# ab73287.net
KiCad netlist of a schematic drawn in EAGLE
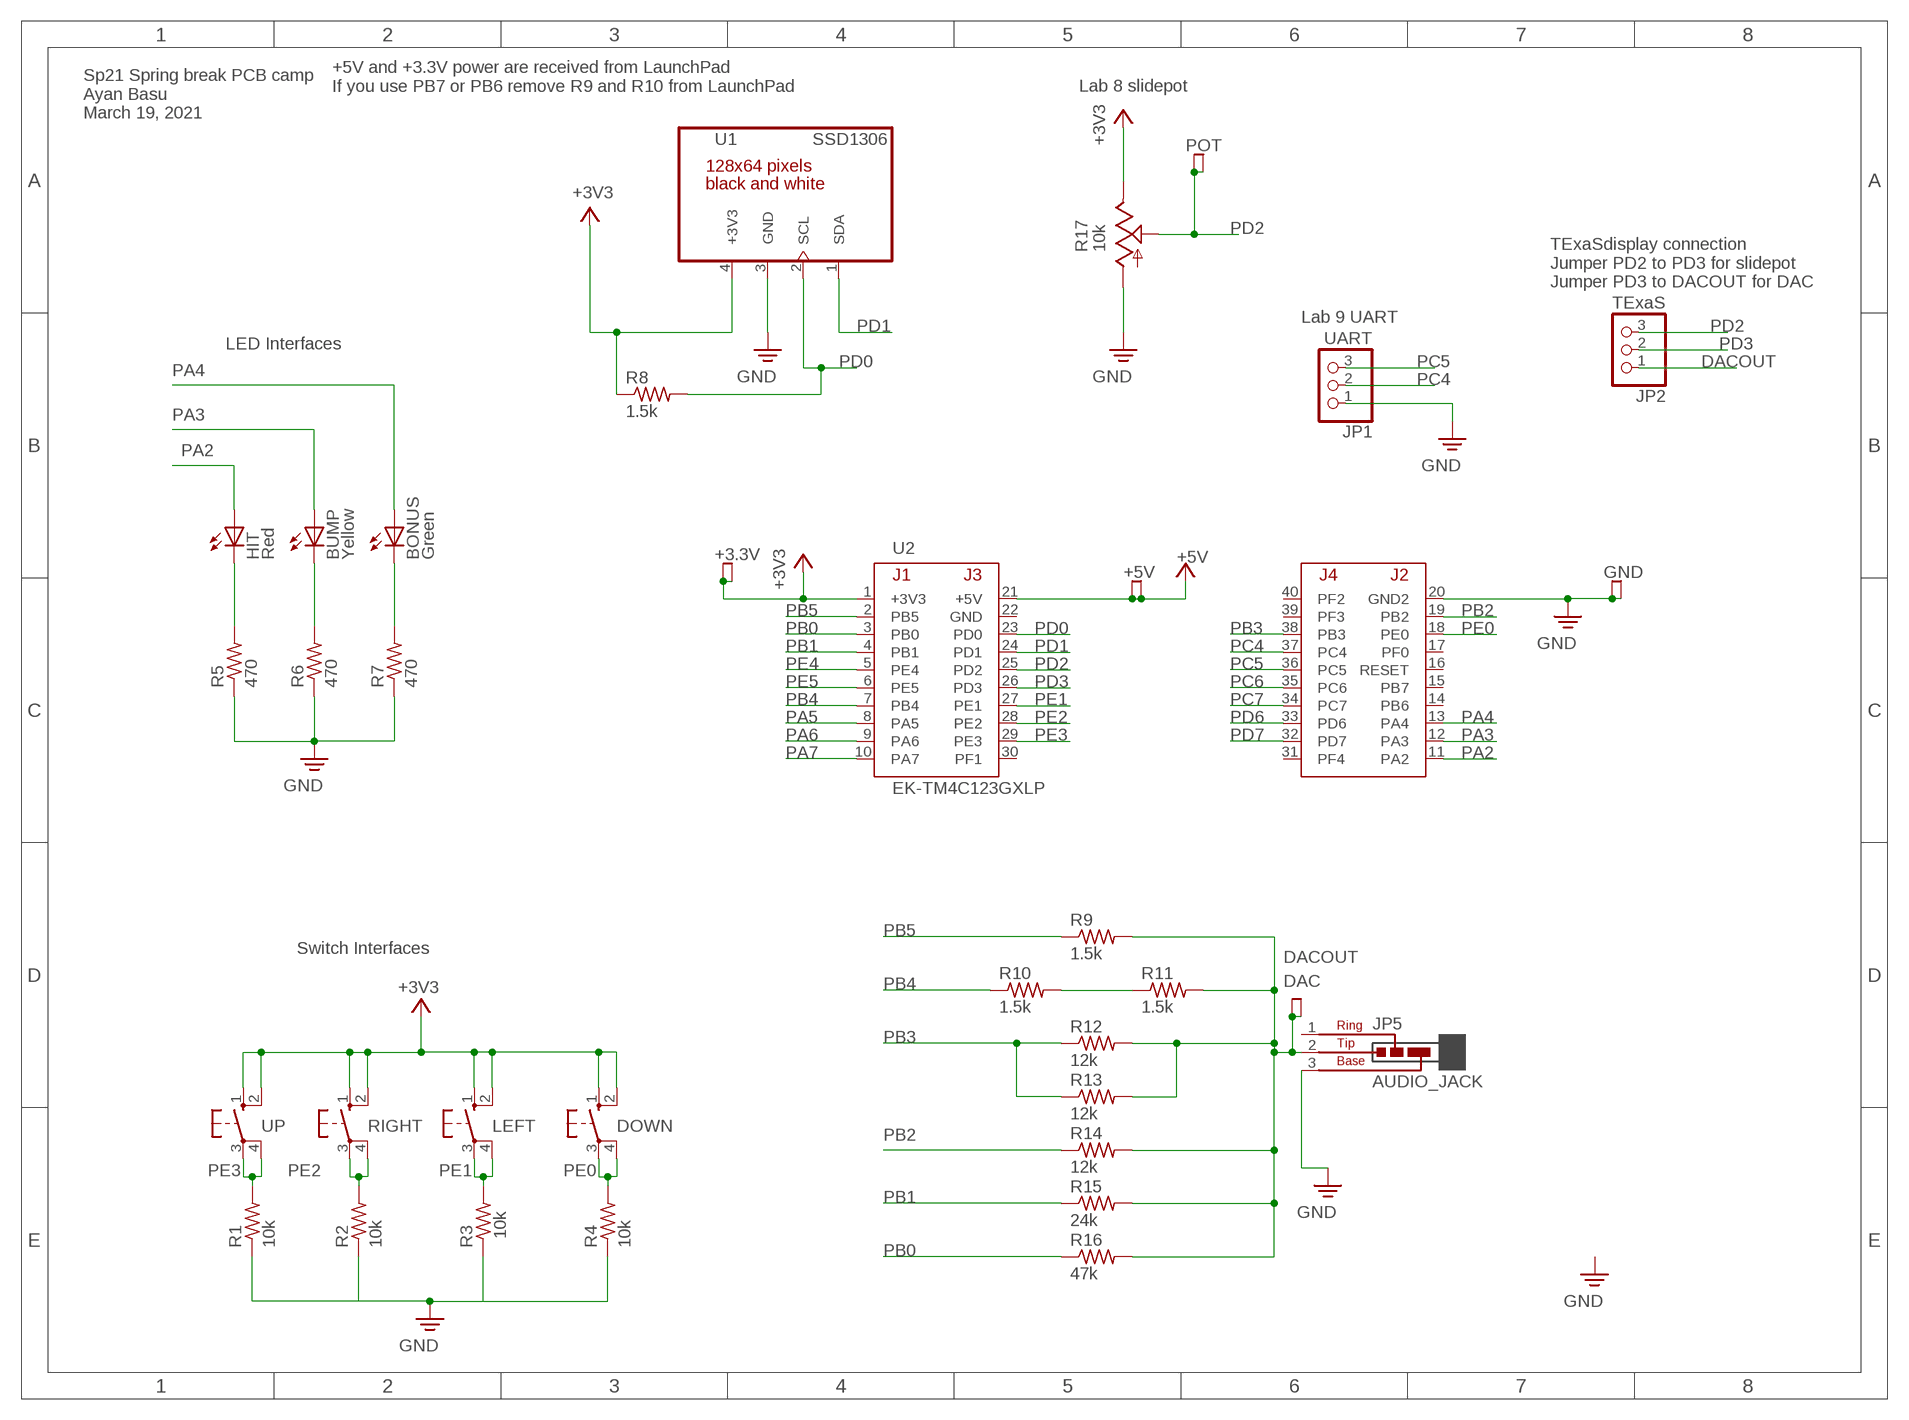
[diagram p0: schematic, sheet 1]

(export (version "E")
  (design (tool "Eeschema 10.0.6"))
  (components
    (comp (ref "+3.3V")
      (value "TP2")
      (footprint "eagle-import:TP2")
      (libsource (lib "eagle-import") (part "TP2"))
    )
    (comp (ref "+5V")
      (value "TP2")
      (footprint "eagle-import:TP2")
      (libsource (lib "eagle-import") (part "TP2"))
    )
    (comp (ref "BONUS")
      (value "Green")
      (footprint "eagle-import:LED5MM")
      (libsource (lib "eagle-import") (part "LED5MM"))
    )
    (comp (ref "BUMP")
      (value "Yellow")
      (footprint "eagle-import:LED5MM")
      (libsource (lib "eagle-import") (part "LED5MM"))
    )
    (comp (ref "DAC")
      (value "TP2")
      (footprint "eagle-import:TP2")
      (libsource (lib "eagle-import") (part "TP2"))
    )
    (comp (ref "DOWN")
      (value "B3F-1052")
      (footprint "eagle-import:B3F-10XX")
      (fields (field (name "MPN") "B3F-1000"))
      (libsource (lib "eagle-import") (part "B3F-1052"))
    )
    (comp (ref "GND")
      (value "TP2")
      (footprint "eagle-import:TP2")
      (libsource (lib "eagle-import") (part "TP2"))
    )
    (comp (ref "HIT")
      (value "Red")
      (footprint "eagle-import:LED5MM")
      (libsource (lib "eagle-import") (part "LED5MM"))
    )
    (comp (ref "JP1")
      (value "UART")
      (footprint "eagle-import:1X03")
      (libsource (lib "eagle-import") (part "PINHD-1X3"))
    )
    (comp (ref "JP2")
      (value "TExaS")
      (footprint "eagle-import:1X03")
      (libsource (lib "eagle-import") (part "PINHD-1X3"))
    )
    (comp (ref "JP5")
      (value "AUDIO_JACK")
      (footprint "eagle-import:JACK")
      (libsource (lib "eagle-import") (part "AUDIO_JACK"))
    )
    (comp (ref "LEFT")
      (value "B3F-1052")
      (footprint "eagle-import:B3F-10XX")
      (fields (field (name "MPN") "B3F-1000"))
      (libsource (lib "eagle-import") (part "B3F-1052"))
    )
    (comp (ref "POT")
      (value "TP2")
      (footprint "eagle-import:TP2")
      (libsource (lib "eagle-import") (part "TP2"))
    )
    (comp (ref "R1")
      (value "10k")
      (footprint "eagle-import:RES300MIL")
      (libsource (lib "eagle-import") (part "RESISTOR0204/7"))
    )
    (comp (ref "R2")
      (value "10k")
      (footprint "eagle-import:RES300MIL")
      (libsource (lib "eagle-import") (part "RESISTOR0204/7"))
    )
    (comp (ref "R3")
      (value "10k")
      (footprint "eagle-import:RES300MIL")
      (libsource (lib "eagle-import") (part "RESISTOR0204/7"))
    )
    (comp (ref "R4")
      (value "10k")
      (footprint "eagle-import:RES300MIL")
      (libsource (lib "eagle-import") (part "RESISTOR0204/7"))
    )
    (comp (ref "R5")
      (value "470")
      (footprint "eagle-import:RES300MIL")
      (libsource (lib "eagle-import") (part "RESISTOR0204/7"))
    )
    (comp (ref "R6")
      (value "470")
      (footprint "eagle-import:RES300MIL")
      (libsource (lib "eagle-import") (part "RESISTOR0204/7"))
    )
    (comp (ref "R7")
      (value "470")
      (footprint "eagle-import:RES300MIL")
      (libsource (lib "eagle-import") (part "RESISTOR0204/7"))
    )
    (comp (ref "R8")
      (value "1.5k")
      (footprint "eagle-import:RES300MIL")
      (libsource (lib "eagle-import") (part "RESISTOR0204/7"))
    )
    (comp (ref "R9")
      (value "1.5k")
      (footprint "eagle-import:RES300MIL")
      (libsource (lib "eagle-import") (part "RESISTOR0204/7"))
    )
    (comp (ref "R10")
      (value "1.5k")
      (footprint "eagle-import:RES300MIL")
      (libsource (lib "eagle-import") (part "RESISTOR0204/7"))
    )
    (comp (ref "R11")
      (value "1.5k")
      (footprint "eagle-import:RES300MIL")
      (libsource (lib "eagle-import") (part "RESISTOR0204/7"))
    )
    (comp (ref "R12")
      (value "12k")
      (footprint "eagle-import:RES300MIL")
      (libsource (lib "eagle-import") (part "RESISTOR0204/7"))
    )
    (comp (ref "R13")
      (value "12k")
      (footprint "eagle-import:RES300MIL")
      (libsource (lib "eagle-import") (part "RESISTOR0204/7"))
    )
    (comp (ref "R14")
      (value "12k")
      (footprint "eagle-import:RES300MIL")
      (libsource (lib "eagle-import") (part "RESISTOR0204/7"))
    )
    (comp (ref "R15")
      (value "24k")
      (footprint "eagle-import:RES300MIL")
      (libsource (lib "eagle-import") (part "RESISTOR0204/7"))
    )
    (comp (ref "R16")
      (value "47k")
      (footprint "eagle-import:RES300MIL")
      (libsource (lib "eagle-import") (part "RESISTOR0204/7"))
    )
    (comp (ref "R17")
      (value "10k")
      (footprint "eagle-import:B25U")
      (libsource (lib "eagle-import") (part "POTENTIOMETERB25U"))
    )
    (comp (ref "RIGHT")
      (value "B3F-1052")
      (footprint "eagle-import:B3F-10XX")
      (fields (field (name "MPN") "B3F-1000"))
      (libsource (lib "eagle-import") (part "B3F-1052"))
    )
    (comp (ref "U1")
      (value "SSD1306")
      (footprint "eagle-import:SSD1306")
      (libsource (lib "eagle-import") (part "SSD1306"))
    )
    (comp (ref "U2")
      (value "EK-TM4C123GXLP")
      (footprint "eagle-import:TM4C123LAUNCHPAD")
      (libsource (lib "eagle-import") (part "EK-TM4C123GXLP"))
    )
    (comp (ref "UP")
      (value "B3F-1052")
      (footprint "eagle-import:B3F-10XX")
      (fields (field (name "MPN") "B3F-1000"))
      (libsource (lib "eagle-import") (part "B3F-1052"))
    )
  )
  (nets
    (net (code "1") (name "+3V3") (class "Default")
      (node (ref "+3.3V") (pin "MP") (pinfunction "TPA_MP") (pintype "passive"))
      (node (ref "+3.3V") (pin "MP1") (pinfunction "TPB_MP1") (pintype "passive"))
      (node (ref "DOWN") (pin "1") (pinfunction "S_1") (pintype "passive"))
      (node (ref "DOWN") (pin "2") (pinfunction "S1_2") (pintype "passive"))
      (node (ref "LEFT") (pin "1") (pinfunction "S_1") (pintype "passive"))
      (node (ref "LEFT") (pin "2") (pinfunction "S1_2") (pintype "passive"))
      (node (ref "R17") (pin "1") (pinfunction "E_1") (pintype "passive"))
      (node (ref "R8") (pin "1") (pinfunction "1_1") (pintype "passive"))
      (node (ref "RIGHT") (pin "1") (pinfunction "S_1") (pintype "passive"))
      (node (ref "RIGHT") (pin "2") (pinfunction "S1_2") (pintype "passive"))
      (node (ref "U1") (pin "4") (pinfunction "+3V3_4") (pintype "power_in"))
      (node (ref "U2") (pin "1") (pinfunction "+3V3_1") (pintype "bidirectional"))
      (node (ref "UP") (pin "1") (pinfunction "S_1") (pintype "passive"))
      (node (ref "UP") (pin "2") (pinfunction "S1_2") (pintype "passive"))
    )
    (net (code "2") (name "+5V") (class "Default")
      (node (ref "+5V") (pin "MP") (pinfunction "TPA_MP") (pintype "passive"))
      (node (ref "+5V") (pin "MP1") (pinfunction "TPB_MP1") (pintype "passive"))
      (node (ref "U2") (pin "21") (pinfunction "+5V_21") (pintype "bidirectional"))
    )
    (net (code "3") (name "/DACOUT") (class "Default")
      (node (ref "DAC") (pin "MP") (pinfunction "TPA_MP") (pintype "passive"))
      (node (ref "DAC") (pin "MP1") (pinfunction "TPB_MP1") (pintype "passive"))
      (node (ref "JP2") (pin "1") (pinfunction "1_1") (pintype "passive"))
      (node (ref "JP5") (pin "2") (pinfunction "TIP_2") (pintype "passive"))
      (node (ref "R11") (pin "2") (pinfunction "2_2") (pintype "passive"))
      (node (ref "R12") (pin "2") (pinfunction "2_2") (pintype "passive"))
      (node (ref "R13") (pin "2") (pinfunction "2_2") (pintype "passive"))
      (node (ref "R14") (pin "2") (pinfunction "2_2") (pintype "passive"))
      (node (ref "R15") (pin "2") (pinfunction "2_2") (pintype "passive"))
      (node (ref "R16") (pin "2") (pinfunction "2_2") (pintype "passive"))
      (node (ref "R9") (pin "2") (pinfunction "2_2") (pintype "passive"))
    )
    (net (code "4") (name "/PA2") (class "Default")
      (node (ref "HIT") (pin "A") (pinfunction "A_A") (pintype "passive"))
      (node (ref "U2") (pin "11") (pinfunction "PA2_11") (pintype "bidirectional"))
    )
    (net (code "5") (name "/PA3") (class "Default")
      (node (ref "BUMP") (pin "A") (pinfunction "A_A") (pintype "passive"))
      (node (ref "U2") (pin "12") (pinfunction "PA3_12") (pintype "bidirectional"))
    )
    (net (code "6") (name "/PA4") (class "Default")
      (node (ref "BONUS") (pin "A") (pinfunction "A_A") (pintype "passive"))
      (node (ref "U2") (pin "13") (pinfunction "PA4_13") (pintype "bidirectional"))
    )
    (net (code "7") (name "/PA5") (class "Default")
      (node (ref "U2") (pin "8") (pinfunction "PA5_8") (pintype "bidirectional"))
    )
    (net (code "8") (name "/PA6") (class "Default")
      (node (ref "U2") (pin "9") (pinfunction "PA6_9") (pintype "bidirectional"))
    )
    (net (code "9") (name "/PA7") (class "Default")
      (node (ref "U2") (pin "10") (pinfunction "PA7_10") (pintype "bidirectional"))
    )
    (net (code "10") (name "/PB0") (class "Default")
      (node (ref "R16") (pin "1") (pinfunction "1_1") (pintype "passive"))
      (node (ref "U2") (pin "3") (pinfunction "PB0_3") (pintype "bidirectional"))
    )
    (net (code "11") (name "/PB1") (class "Default")
      (node (ref "R15") (pin "1") (pinfunction "1_1") (pintype "passive"))
      (node (ref "U2") (pin "4") (pinfunction "PB1_4") (pintype "bidirectional"))
    )
    (net (code "12") (name "/PB2") (class "Default")
      (node (ref "R14") (pin "1") (pinfunction "1_1") (pintype "passive"))
      (node (ref "U2") (pin "19") (pinfunction "PB2_19") (pintype "bidirectional"))
    )
    (net (code "13") (name "/PB3") (class "Default")
      (node (ref "R12") (pin "1") (pinfunction "1_1") (pintype "passive"))
      (node (ref "R13") (pin "1") (pinfunction "1_1") (pintype "passive"))
      (node (ref "U2") (pin "38") (pinfunction "PB3_38") (pintype "bidirectional"))
    )
    (net (code "14") (name "/PB4") (class "Default")
      (node (ref "R10") (pin "1") (pinfunction "1_1") (pintype "passive"))
      (node (ref "U2") (pin "7") (pinfunction "PB4_7") (pintype "bidirectional"))
    )
    (net (code "15") (name "/PB5") (class "Default")
      (node (ref "R9") (pin "1") (pinfunction "1_1") (pintype "passive"))
      (node (ref "U2") (pin "2") (pinfunction "PB5_2") (pintype "bidirectional"))
    )
    (net (code "16") (name "/PC4") (class "Default")
      (node (ref "JP1") (pin "2") (pinfunction "2_2") (pintype "passive"))
      (node (ref "U2") (pin "37") (pinfunction "PC4_37") (pintype "bidirectional"))
    )
    (net (code "17") (name "/PC5") (class "Default")
      (node (ref "JP1") (pin "3") (pinfunction "3_3") (pintype "passive"))
      (node (ref "U2") (pin "36") (pinfunction "PC5_36") (pintype "bidirectional"))
    )
    (net (code "18") (name "/PC6") (class "Default")
      (node (ref "U2") (pin "35") (pinfunction "PC6_35") (pintype "bidirectional"))
    )
    (net (code "19") (name "/PC7") (class "Default")
      (node (ref "U2") (pin "34") (pinfunction "PC7_34") (pintype "bidirectional"))
    )
    (net (code "20") (name "/PD0") (class "Default")
      (node (ref "R8") (pin "2") (pinfunction "2_2") (pintype "passive"))
      (node (ref "U1") (pin "2") (pinfunction "SCL_2") (pintype "input"))
      (node (ref "U2") (pin "23") (pinfunction "PD0_23") (pintype "bidirectional"))
    )
    (net (code "21") (name "/PD1") (class "Default")
      (node (ref "U1") (pin "1") (pinfunction "SDA_1") (pintype "input"))
      (node (ref "U2") (pin "24") (pinfunction "PD1_24") (pintype "bidirectional"))
    )
    (net (code "22") (name "/PD2") (class "Default")
      (node (ref "JP2") (pin "3") (pinfunction "3_3") (pintype "passive"))
      (node (ref "POT") (pin "MP") (pinfunction "TPA_MP") (pintype "passive"))
      (node (ref "POT") (pin "MP1") (pinfunction "TPB_MP1") (pintype "passive"))
      (node (ref "R17") (pin "2") (pinfunction "S_2") (pintype "passive"))
      (node (ref "U2") (pin "25") (pinfunction "PD2_25") (pintype "bidirectional"))
    )
    (net (code "23") (name "/PD3") (class "Default")
      (node (ref "JP2") (pin "2") (pinfunction "2_2") (pintype "passive"))
      (node (ref "U2") (pin "26") (pinfunction "PD3_26") (pintype "bidirectional"))
    )
    (net (code "24") (name "/PD6") (class "Default")
      (node (ref "U2") (pin "33") (pinfunction "PD6_33") (pintype "bidirectional"))
    )
    (net (code "25") (name "/PD7") (class "Default")
      (node (ref "U2") (pin "32") (pinfunction "PD7_32") (pintype "bidirectional"))
    )
    (net (code "26") (name "/PE0") (class "Default")
      (node (ref "DOWN") (pin "3") (pinfunction "P_3") (pintype "passive"))
      (node (ref "DOWN") (pin "4") (pinfunction "P1_4") (pintype "passive"))
      (node (ref "R4") (pin "2") (pinfunction "2_2") (pintype "passive"))
      (node (ref "U2") (pin "18") (pinfunction "PE0_18") (pintype "bidirectional"))
    )
    (net (code "27") (name "/PE1") (class "Default")
      (node (ref "LEFT") (pin "3") (pinfunction "P_3") (pintype "passive"))
      (node (ref "LEFT") (pin "4") (pinfunction "P1_4") (pintype "passive"))
      (node (ref "R3") (pin "2") (pinfunction "2_2") (pintype "passive"))
      (node (ref "U2") (pin "27") (pinfunction "PE1_27") (pintype "bidirectional"))
    )
    (net (code "28") (name "/PE2") (class "Default")
      (node (ref "R2") (pin "2") (pinfunction "2_2") (pintype "passive"))
      (node (ref "RIGHT") (pin "3") (pinfunction "P_3") (pintype "passive"))
      (node (ref "RIGHT") (pin "4") (pinfunction "P1_4") (pintype "passive"))
      (node (ref "U2") (pin "28") (pinfunction "PE2_28") (pintype "bidirectional"))
    )
    (net (code "29") (name "/PE3") (class "Default")
      (node (ref "R1") (pin "2") (pinfunction "2_2") (pintype "passive"))
      (node (ref "U2") (pin "29") (pinfunction "PE3_29") (pintype "bidirectional"))
      (node (ref "UP") (pin "3") (pinfunction "P_3") (pintype "passive"))
      (node (ref "UP") (pin "4") (pinfunction "P1_4") (pintype "passive"))
    )
    (net (code "30") (name "/PE4") (class "Default")
      (node (ref "U2") (pin "5") (pinfunction "PE4_5") (pintype "bidirectional"))
    )
    (net (code "31") (name "/PE5") (class "Default")
      (node (ref "U2") (pin "6") (pinfunction "PE5_6") (pintype "bidirectional"))
    )
    (net (code "32") (name "GND") (class "Default")
      (node (ref "GND") (pin "MP") (pinfunction "TPA_MP") (pintype "passive"))
      (node (ref "GND") (pin "MP1") (pinfunction "TPB_MP1") (pintype "passive"))
      (node (ref "JP1") (pin "1") (pinfunction "1_1") (pintype "passive"))
      (node (ref "JP5") (pin "3") (pinfunction "BASE_3") (pintype "passive"))
      (node (ref "R1") (pin "1") (pinfunction "1_1") (pintype "passive"))
      (node (ref "R17") (pin "3") (pinfunction "A_3") (pintype "passive"))
      (node (ref "R2") (pin "1") (pinfunction "1_1") (pintype "passive"))
      (node (ref "R3") (pin "1") (pinfunction "1_1") (pintype "passive"))
      (node (ref "R4") (pin "1") (pinfunction "1_1") (pintype "passive"))
      (node (ref "R5") (pin "1") (pinfunction "1_1") (pintype "passive"))
      (node (ref "R6") (pin "1") (pinfunction "1_1") (pintype "passive"))
      (node (ref "R7") (pin "1") (pinfunction "1_1") (pintype "passive"))
      (node (ref "U1") (pin "3") (pinfunction "GND_3") (pintype "power_in"))
      (node (ref "U2") (pin "20") (pinfunction "GND2_20") (pintype "bidirectional"))
    )
    (net (code "33") (name "Net-(BONUS-C)") (class "Default")
      (node (ref "BONUS") (pin "K") (pinfunction "C_K") (pintype "passive"))
      (node (ref "R7") (pin "2") (pinfunction "2_2") (pintype "passive"))
    )
    (net (code "34") (name "Net-(BUMP-C)") (class "Default")
      (node (ref "BUMP") (pin "K") (pinfunction "C_K") (pintype "passive"))
      (node (ref "R6") (pin "2") (pinfunction "2_2") (pintype "passive"))
    )
    (net (code "35") (name "Net-(HIT-C)") (class "Default")
      (node (ref "HIT") (pin "K") (pinfunction "C_K") (pintype "passive"))
      (node (ref "R5") (pin "2") (pinfunction "2_2") (pintype "passive"))
    )
    (net (code "36") (name "Net-(R10-Pad2)") (class "Default")
      (node (ref "R10") (pin "2") (pinfunction "2_2") (pintype "passive"))
      (node (ref "R11") (pin "1") (pinfunction "1_1") (pintype "passive"))
    )
    (net (code "37") (name "unconnected-(JP5-RING-Pad1)") (class "Default")
      (node (ref "JP5") (pin "1") (pinfunction "RING_1") (pintype "passive"))
    )
    (net (code "38") (name "unconnected-(U2-GND-Pad22)") (class "Default")
      (node (ref "U2") (pin "22") (pinfunction "GND_22") (pintype "bidirectional"))
    )
    (net (code "39") (name "unconnected-(U2-PB6-Pad14)") (class "Default")
      (node (ref "U2") (pin "14") (pinfunction "PB6_14") (pintype "bidirectional"))
    )
    (net (code "40") (name "unconnected-(U2-PB7-Pad15)") (class "Default")
      (node (ref "U2") (pin "15") (pinfunction "PB7_15") (pintype "bidirectional"))
    )
    (net (code "41") (name "unconnected-(U2-PF0-Pad17)") (class "Default")
      (node (ref "U2") (pin "17") (pinfunction "PF0_17") (pintype "bidirectional"))
    )
    (net (code "42") (name "unconnected-(U2-PF1-Pad30)") (class "Default")
      (node (ref "U2") (pin "30") (pinfunction "PF1_30") (pintype "bidirectional"))
    )
    (net (code "43") (name "unconnected-(U2-PF2-Pad40)") (class "Default")
      (node (ref "U2") (pin "40") (pinfunction "PF2_40") (pintype "bidirectional"))
    )
    (net (code "44") (name "unconnected-(U2-PF3-Pad39)") (class "Default")
      (node (ref "U2") (pin "39") (pinfunction "PF3_39") (pintype "bidirectional"))
    )
    (net (code "45") (name "unconnected-(U2-PF4-Pad31)") (class "Default")
      (node (ref "U2") (pin "31") (pinfunction "PF4_31") (pintype "bidirectional"))
    )
    (net (code "46") (name "unconnected-(U2-RESET-Pad16)") (class "Default")
      (node (ref "U2") (pin "16") (pinfunction "RESET_16") (pintype "bidirectional"))
    )
  )
)
